# due_canshield.net
KiCad netlist of a schematic drawn in EAGLE
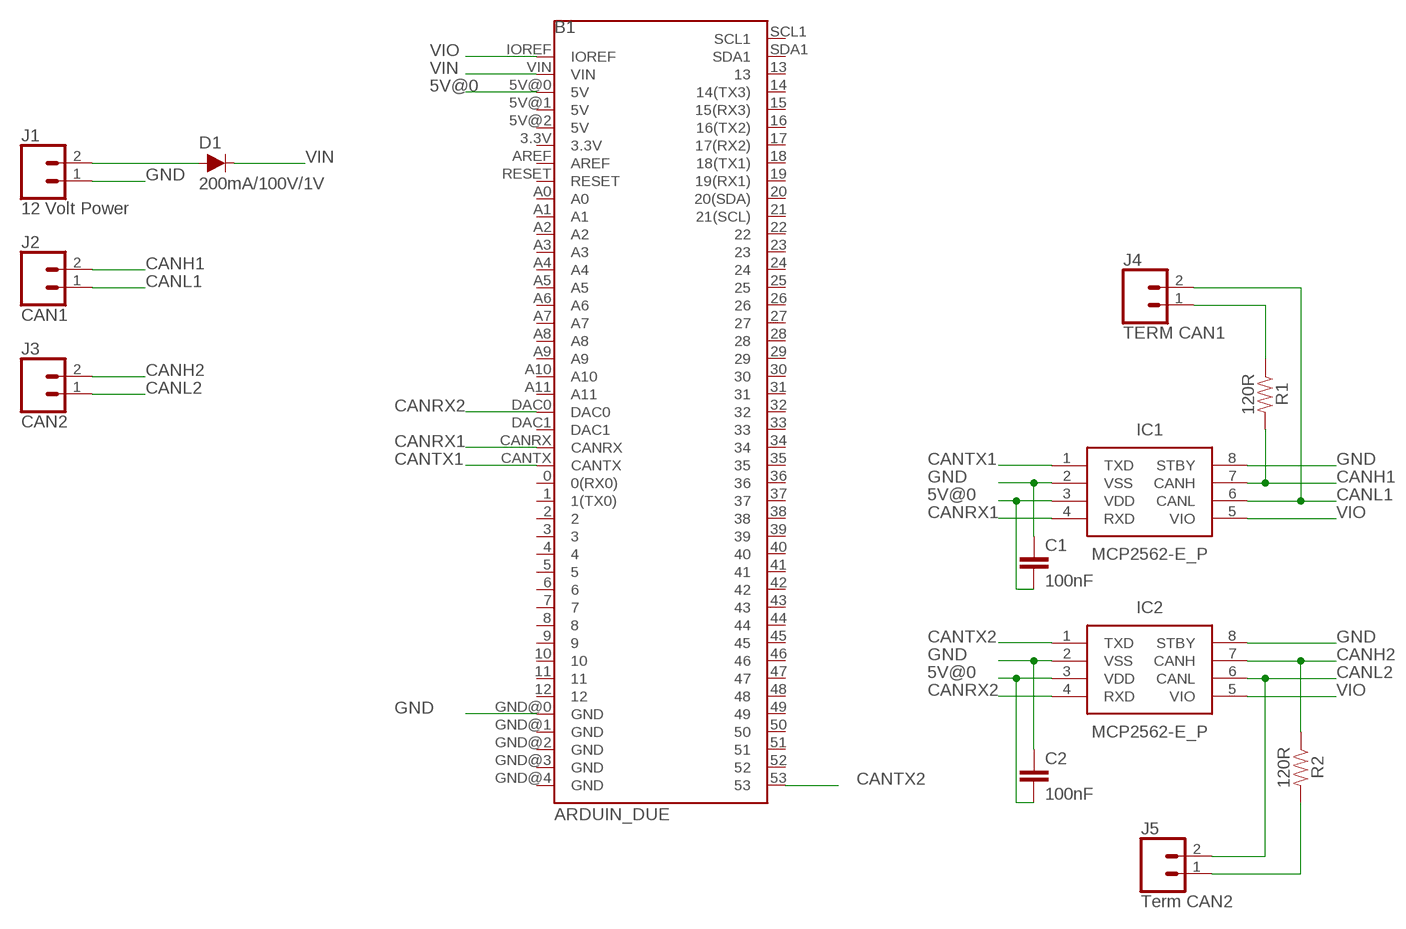
[diagram p0: schematic, sheet 1]

(export (version "E")
  (design (tool "Eeschema 10.0.6"))
  (components
    (comp (ref "B1")
      (value "ARDUIN_DUE")
      (footprint "eagle-import:ARDUINODUE")
      (libsource (lib "eagle-import") (part "ARDUIN_DUE"))
    )
    (comp (ref "C1")
      (value "100nF")
      (footprint "eagle-import:CAP-PTH-10MM")
      (libsource (lib "eagle-import") (part "10NF-PTH-10MM-10000V-1-%"))
    )
    (comp (ref "C2")
      (value "100nF")
      (footprint "eagle-import:CAP-PTH-10MM")
      (libsource (lib "eagle-import") (part "10NF-PTH-10MM-10000V-1-%"))
    )
    (comp (ref "D1")
      (value "200mA/100V/1V")
      (footprint "eagle-import:DIODE-1N4148")
      (libsource (lib "eagle-import") (part "DIODE-1N4148"))
    )
    (comp (ref "IC1")
      (value "MCP2562-E_P")
      (footprint "eagle-import:DIP781W56P254L950H533Q8N")
      (fields
        (field (name "MANUFACTURER_PART_NUMBER") "MCP2562-E/P")
        (field (name "RS_PART_NUMBER") "7990225")
      )
      (libsource (lib "eagle-import") (part "MCP2562-E_P"))
    )
    (comp (ref "IC2")
      (value "MCP2562-E_P")
      (footprint "eagle-import:DIP781W56P254L950H533Q8N")
      (fields
        (field (name "MANUFACTURER_PART_NUMBER") "MCP2562-E/P")
        (field (name "RS_PART_NUMBER") "7990225")
      )
      (libsource (lib "eagle-import") (part "MCP2562-E_P"))
    )
    (comp (ref "J1")
      (value "12 Volt Power")
      (footprint "eagle-import:SCREWTERMINAL-3.5MM-2")
      (libsource (lib "eagle-import") (part "SparkFun-Retired_CONN_023.5MM"))
    )
    (comp (ref "J2")
      (value "CAN1")
      (footprint "eagle-import:SCREWTERMINAL-3.5MM-2")
      (libsource (lib "eagle-import") (part "SparkFun-Retired_CONN_023.5MM"))
    )
    (comp (ref "J3")
      (value "CAN2")
      (footprint "eagle-import:SCREWTERMINAL-3.5MM-2")
      (libsource (lib "eagle-import") (part "SparkFun-Retired_CONN_023.5MM"))
    )
    (comp (ref "J4")
      (value "TERM CAN1")
      (footprint "eagle-import:1X02_LOCK_LONGPADS")
      (libsource (lib "eagle-import") (part "CONN_02LOCK_LONGPADS"))
    )
    (comp (ref "J5")
      (value "Term CAN2")
      (footprint "eagle-import:1X02_LOCK_LONGPADS")
      (libsource (lib "eagle-import") (part "CONN_02LOCK_LONGPADS"))
    )
    (comp (ref "R1")
      (value "120R")
      (footprint "eagle-import:AXIAL-0.3")
      (libsource (lib "eagle-import") (part "1KOHM-HORIZ-1/4W-5%"))
    )
    (comp (ref "R2")
      (value "120R")
      (footprint "eagle-import:AXIAL-0.3")
      (libsource (lib "eagle-import") (part "1KOHM-HORIZ-1/4W-5%"))
    )
  )
  (nets
    (net (code "1") (name "/5V@0") (class "Default")
      (node (ref "B1") (pin "5V@0") (pinfunction "5V_5V@0") (pintype "bidirectional"))
      (node (ref "C1") (pin "2") (pinfunction "2_2") (pintype "passive"))
      (node (ref "C2") (pin "2") (pinfunction "2_2") (pintype "passive"))
      (node (ref "IC1") (pin "3") (pinfunction "VDD_3") (pintype "passive"))
      (node (ref "IC2") (pin "3") (pinfunction "VDD_3") (pintype "passive"))
    )
    (net (code "2") (name "/CANH1") (class "Default")
      (node (ref "IC1") (pin "7") (pinfunction "CANH_7") (pintype "passive"))
      (node (ref "J2") (pin "2") (pinfunction "2_2") (pintype "passive"))
      (node (ref "R1") (pin "P$2") (pinfunction "2_P$2") (pintype "passive"))
    )
    (net (code "3") (name "/CANH2") (class "Default")
      (node (ref "IC2") (pin "7") (pinfunction "CANH_7") (pintype "passive"))
      (node (ref "J3") (pin "2") (pinfunction "2_2") (pintype "passive"))
      (node (ref "R2") (pin "P$1") (pinfunction "1_P$1") (pintype "passive"))
    )
    (net (code "4") (name "/CANL1") (class "Default")
      (node (ref "IC1") (pin "6") (pinfunction "CANL_6") (pintype "passive"))
      (node (ref "J2") (pin "1") (pinfunction "1_1") (pintype "passive"))
      (node (ref "J4") (pin "2") (pinfunction "2_2") (pintype "passive"))
    )
    (net (code "5") (name "/CANL2") (class "Default")
      (node (ref "IC2") (pin "6") (pinfunction "CANL_6") (pintype "passive"))
      (node (ref "J3") (pin "1") (pinfunction "1_1") (pintype "passive"))
      (node (ref "J5") (pin "2") (pinfunction "2_2") (pintype "passive"))
    )
    (net (code "6") (name "/CANRX1") (class "Default")
      (node (ref "B1") (pin "CANRX") (pinfunction "CANRX_CANRX") (pintype "bidirectional"))
      (node (ref "IC1") (pin "4") (pinfunction "RXD_4") (pintype "passive"))
    )
    (net (code "7") (name "/CANRX2") (class "Default")
      (node (ref "B1") (pin "DAC0") (pinfunction "DAC0_DAC0") (pintype "bidirectional"))
      (node (ref "IC2") (pin "4") (pinfunction "RXD_4") (pintype "passive"))
    )
    (net (code "8") (name "/CANTX1") (class "Default")
      (node (ref "B1") (pin "CANTX") (pinfunction "CANTX_CANTX") (pintype "bidirectional"))
      (node (ref "IC1") (pin "1") (pinfunction "TXD_1") (pintype "passive"))
    )
    (net (code "9") (name "/CANTX2") (class "Default")
      (node (ref "B1") (pin "53") (pinfunction "53_53") (pintype "bidirectional"))
      (node (ref "IC2") (pin "1") (pinfunction "TXD_1") (pintype "passive"))
    )
    (net (code "10") (name "/GND") (class "Default")
      (node (ref "B1") (pin "GND@0") (pinfunction "GND_GND@0") (pintype "bidirectional"))
      (node (ref "C1") (pin "1") (pinfunction "1_1") (pintype "passive"))
      (node (ref "C2") (pin "1") (pinfunction "1_1") (pintype "passive"))
      (node (ref "IC1") (pin "2") (pinfunction "VSS_2") (pintype "passive"))
      (node (ref "IC1") (pin "8") (pinfunction "STBY_8") (pintype "passive"))
      (node (ref "IC2") (pin "2") (pinfunction "VSS_2") (pintype "passive"))
      (node (ref "IC2") (pin "8") (pinfunction "STBY_8") (pintype "passive"))
      (node (ref "J1") (pin "1") (pinfunction "1_1") (pintype "passive"))
    )
    (net (code "11") (name "/VIN") (class "Default")
      (node (ref "B1") (pin "VIN") (pinfunction "VIN_VIN") (pintype "bidirectional"))
      (node (ref "D1") (pin "C") (pinfunction "C_C") (pintype "passive"))
    )
    (net (code "12") (name "/VIO") (class "Default")
      (node (ref "B1") (pin "IOREF") (pinfunction "IOREF_IOREF") (pintype "bidirectional"))
      (node (ref "IC1") (pin "5") (pinfunction "VIO_5") (pintype "passive"))
      (node (ref "IC2") (pin "5") (pinfunction "VIO_5") (pintype "passive"))
    )
    (net (code "13") (name "Net-(D1-PadA)") (class "Default")
      (node (ref "D1") (pin "A") (pinfunction "A_A") (pintype "passive"))
      (node (ref "J1") (pin "2") (pinfunction "2_2") (pintype "passive"))
    )
    (net (code "14") (name "Net-(R1-1)") (class "Default")
      (node (ref "J4") (pin "1") (pinfunction "1_1") (pintype "passive"))
      (node (ref "R1") (pin "P$1") (pinfunction "1_P$1") (pintype "passive"))
    )
    (net (code "15") (name "Net-(R2-2)") (class "Default")
      (node (ref "J5") (pin "1") (pinfunction "1_1") (pintype "passive"))
      (node (ref "R2") (pin "P$2") (pinfunction "2_P$2") (pintype "passive"))
    )
    (net (code "16") (name "unconnected-(B1-0(RX0)-Pad0)") (class "Default")
      (node (ref "B1") (pin "0") (pinfunction "0(RX0)_0") (pintype "bidirectional"))
    )
    (net (code "17") (name "unconnected-(B1-1(TX0)-Pad1)") (class "Default")
      (node (ref "B1") (pin "1") (pinfunction "1(TX0)_1") (pintype "bidirectional"))
    )
    (net (code "18") (name "unconnected-(B1-5V-Pad5V@1)") (class "Default")
      (node (ref "B1") (pin "5V@1") (pinfunction "5V_5V@1") (pintype "bidirectional"))
    )
    (net (code "19") (name "unconnected-(B1-5V-Pad5V@2)") (class "Default")
      (node (ref "B1") (pin "5V@2") (pinfunction "5V_5V@2") (pintype "bidirectional"))
    )
    (net (code "20") (name "unconnected-(B1-14(TX3)-Pad14)") (class "Default")
      (node (ref "B1") (pin "14") (pinfunction "14(TX3)_14") (pintype "bidirectional"))
    )
    (net (code "21") (name "unconnected-(B1-15(RX3)-Pad15)") (class "Default")
      (node (ref "B1") (pin "15") (pinfunction "15(RX3)_15") (pintype "bidirectional"))
    )
    (net (code "22") (name "unconnected-(B1-16(TX2)-Pad16)") (class "Default")
      (node (ref "B1") (pin "16") (pinfunction "16(TX2)_16") (pintype "bidirectional"))
    )
    (net (code "23") (name "unconnected-(B1-17(RX2)-Pad17)") (class "Default")
      (node (ref "B1") (pin "17") (pinfunction "17(RX2)_17") (pintype "bidirectional"))
    )
    (net (code "24") (name "unconnected-(B1-18(TX1)-Pad18)") (class "Default")
      (node (ref "B1") (pin "18") (pinfunction "18(TX1)_18") (pintype "bidirectional"))
    )
    (net (code "25") (name "unconnected-(B1-19(RX1)-Pad19)") (class "Default")
      (node (ref "B1") (pin "19") (pinfunction "19(RX1)_19") (pintype "bidirectional"))
    )
    (net (code "26") (name "unconnected-(B1-20(SDA)-Pad20)") (class "Default")
      (node (ref "B1") (pin "20") (pinfunction "20(SDA)_20") (pintype "bidirectional"))
    )
    (net (code "27") (name "unconnected-(B1-21(SCL)-Pad21)") (class "Default")
      (node (ref "B1") (pin "21") (pinfunction "21(SCL)_21") (pintype "bidirectional"))
    )
    (net (code "28") (name "unconnected-(B1-GND-PadGND@1)") (class "Default")
      (node (ref "B1") (pin "GND@1") (pinfunction "GND_GND@1") (pintype "bidirectional"))
    )
    (net (code "29") (name "unconnected-(B1-GND-PadGND@2)") (class "Default")
      (node (ref "B1") (pin "GND@2") (pinfunction "GND_GND@2") (pintype "bidirectional"))
    )
    (net (code "30") (name "unconnected-(B1-GND-PadGND@3)") (class "Default")
      (node (ref "B1") (pin "GND@3") (pinfunction "GND_GND@3") (pintype "bidirectional"))
    )
    (net (code "31") (name "unconnected-(B1-GND-PadGND@4)") (class "Default")
      (node (ref "B1") (pin "GND@4") (pinfunction "GND_GND@4") (pintype "bidirectional"))
    )
    (net (code "32") (name "unconnected-(B1-Pad2)") (class "Default")
      (node (ref "B1") (pin "2") (pinfunction "2_2") (pintype "bidirectional"))
    )
    (net (code "33") (name "unconnected-(B1-Pad3)") (class "Default")
      (node (ref "B1") (pin "3") (pinfunction "3_3") (pintype "bidirectional"))
    )
    (net (code "34") (name "unconnected-(B1-Pad3.3V)") (class "Default")
      (node (ref "B1") (pin "3.3V") (pinfunction "3.3V_3.3V") (pintype "bidirectional"))
    )
    (net (code "35") (name "unconnected-(B1-Pad4)") (class "Default")
      (node (ref "B1") (pin "4") (pinfunction "4_4") (pintype "bidirectional"))
    )
    (net (code "36") (name "unconnected-(B1-Pad5)") (class "Default")
      (node (ref "B1") (pin "5") (pinfunction "5_5") (pintype "bidirectional"))
    )
    (net (code "37") (name "unconnected-(B1-Pad6)") (class "Default")
      (node (ref "B1") (pin "6") (pinfunction "6_6") (pintype "bidirectional"))
    )
    (net (code "38") (name "unconnected-(B1-Pad7)") (class "Default")
      (node (ref "B1") (pin "7") (pinfunction "7_7") (pintype "bidirectional"))
    )
    (net (code "39") (name "unconnected-(B1-Pad8)") (class "Default")
      (node (ref "B1") (pin "8") (pinfunction "8_8") (pintype "bidirectional"))
    )
    (net (code "40") (name "unconnected-(B1-Pad9)") (class "Default")
      (node (ref "B1") (pin "9") (pinfunction "9_9") (pintype "bidirectional"))
    )
    (net (code "41") (name "unconnected-(B1-Pad10)") (class "Default")
      (node (ref "B1") (pin "10") (pinfunction "10_10") (pintype "bidirectional"))
    )
    (net (code "42") (name "unconnected-(B1-Pad11)") (class "Default")
      (node (ref "B1") (pin "11") (pinfunction "11_11") (pintype "bidirectional"))
    )
    (net (code "43") (name "unconnected-(B1-Pad12)") (class "Default")
      (node (ref "B1") (pin "12") (pinfunction "12_12") (pintype "bidirectional"))
    )
    (net (code "44") (name "unconnected-(B1-Pad13)") (class "Default")
      (node (ref "B1") (pin "13") (pinfunction "13_13") (pintype "bidirectional"))
    )
    (net (code "45") (name "unconnected-(B1-Pad22)") (class "Default")
      (node (ref "B1") (pin "22") (pinfunction "22_22") (pintype "bidirectional"))
    )
    (net (code "46") (name "unconnected-(B1-Pad23)") (class "Default")
      (node (ref "B1") (pin "23") (pinfunction "23_23") (pintype "bidirectional"))
    )
    (net (code "47") (name "unconnected-(B1-Pad24)") (class "Default")
      (node (ref "B1") (pin "24") (pinfunction "24_24") (pintype "bidirectional"))
    )
    (net (code "48") (name "unconnected-(B1-Pad25)") (class "Default")
      (node (ref "B1") (pin "25") (pinfunction "25_25") (pintype "bidirectional"))
    )
    (net (code "49") (name "unconnected-(B1-Pad26)") (class "Default")
      (node (ref "B1") (pin "26") (pinfunction "26_26") (pintype "bidirectional"))
    )
    (net (code "50") (name "unconnected-(B1-Pad27)") (class "Default")
      (node (ref "B1") (pin "27") (pinfunction "27_27") (pintype "bidirectional"))
    )
    (net (code "51") (name "unconnected-(B1-Pad28)") (class "Default")
      (node (ref "B1") (pin "28") (pinfunction "28_28") (pintype "bidirectional"))
    )
    (net (code "52") (name "unconnected-(B1-Pad29)") (class "Default")
      (node (ref "B1") (pin "29") (pinfunction "29_29") (pintype "bidirectional"))
    )
    (net (code "53") (name "unconnected-(B1-Pad30)") (class "Default")
      (node (ref "B1") (pin "30") (pinfunction "30_30") (pintype "bidirectional"))
    )
    (net (code "54") (name "unconnected-(B1-Pad31)") (class "Default")
      (node (ref "B1") (pin "31") (pinfunction "31_31") (pintype "bidirectional"))
    )
    (net (code "55") (name "unconnected-(B1-Pad32)") (class "Default")
      (node (ref "B1") (pin "32") (pinfunction "32_32") (pintype "bidirectional"))
    )
    (net (code "56") (name "unconnected-(B1-Pad33)") (class "Default")
      (node (ref "B1") (pin "33") (pinfunction "33_33") (pintype "bidirectional"))
    )
    (net (code "57") (name "unconnected-(B1-Pad34)") (class "Default")
      (node (ref "B1") (pin "34") (pinfunction "34_34") (pintype "bidirectional"))
    )
    (net (code "58") (name "unconnected-(B1-Pad35)") (class "Default")
      (node (ref "B1") (pin "35") (pinfunction "35_35") (pintype "bidirectional"))
    )
    (net (code "59") (name "unconnected-(B1-Pad36)") (class "Default")
      (node (ref "B1") (pin "36") (pinfunction "36_36") (pintype "bidirectional"))
    )
    (net (code "60") (name "unconnected-(B1-Pad37)") (class "Default")
      (node (ref "B1") (pin "37") (pinfunction "37_37") (pintype "bidirectional"))
    )
    (net (code "61") (name "unconnected-(B1-Pad38)") (class "Default")
      (node (ref "B1") (pin "38") (pinfunction "38_38") (pintype "bidirectional"))
    )
    (net (code "62") (name "unconnected-(B1-Pad39)") (class "Default")
      (node (ref "B1") (pin "39") (pinfunction "39_39") (pintype "bidirectional"))
    )
    (net (code "63") (name "unconnected-(B1-Pad40)") (class "Default")
      (node (ref "B1") (pin "40") (pinfunction "40_40") (pintype "bidirectional"))
    )
    (net (code "64") (name "unconnected-(B1-Pad41)") (class "Default")
      (node (ref "B1") (pin "41") (pinfunction "41_41") (pintype "bidirectional"))
    )
    (net (code "65") (name "unconnected-(B1-Pad42)") (class "Default")
      (node (ref "B1") (pin "42") (pinfunction "42_42") (pintype "bidirectional"))
    )
    (net (code "66") (name "unconnected-(B1-Pad43)") (class "Default")
      (node (ref "B1") (pin "43") (pinfunction "43_43") (pintype "bidirectional"))
    )
    (net (code "67") (name "unconnected-(B1-Pad44)") (class "Default")
      (node (ref "B1") (pin "44") (pinfunction "44_44") (pintype "bidirectional"))
    )
    (net (code "68") (name "unconnected-(B1-Pad45)") (class "Default")
      (node (ref "B1") (pin "45") (pinfunction "45_45") (pintype "bidirectional"))
    )
    (net (code "69") (name "unconnected-(B1-Pad46)") (class "Default")
      (node (ref "B1") (pin "46") (pinfunction "46_46") (pintype "bidirectional"))
    )
    (net (code "70") (name "unconnected-(B1-Pad47)") (class "Default")
      (node (ref "B1") (pin "47") (pinfunction "47_47") (pintype "bidirectional"))
    )
    (net (code "71") (name "unconnected-(B1-Pad48)") (class "Default")
      (node (ref "B1") (pin "48") (pinfunction "48_48") (pintype "bidirectional"))
    )
    (net (code "72") (name "unconnected-(B1-Pad49)") (class "Default")
      (node (ref "B1") (pin "49") (pinfunction "49_49") (pintype "bidirectional"))
    )
    (net (code "73") (name "unconnected-(B1-Pad50)") (class "Default")
      (node (ref "B1") (pin "50") (pinfunction "50_50") (pintype "bidirectional"))
    )
    (net (code "74") (name "unconnected-(B1-Pad51)") (class "Default")
      (node (ref "B1") (pin "51") (pinfunction "51_51") (pintype "bidirectional"))
    )
    (net (code "75") (name "unconnected-(B1-Pad52)") (class "Default")
      (node (ref "B1") (pin "52") (pinfunction "52_52") (pintype "bidirectional"))
    )
    (net (code "76") (name "unconnected-(B1-PadA0)") (class "Default")
      (node (ref "B1") (pin "A0") (pinfunction "A0_A0") (pintype "bidirectional"))
    )
    (net (code "77") (name "unconnected-(B1-PadA1)") (class "Default")
      (node (ref "B1") (pin "A1") (pinfunction "A1_A1") (pintype "bidirectional"))
    )
    (net (code "78") (name "unconnected-(B1-PadA2)") (class "Default")
      (node (ref "B1") (pin "A2") (pinfunction "A2_A2") (pintype "bidirectional"))
    )
    (net (code "79") (name "unconnected-(B1-PadA3)") (class "Default")
      (node (ref "B1") (pin "A3") (pinfunction "A3_A3") (pintype "bidirectional"))
    )
    (net (code "80") (name "unconnected-(B1-PadA4)") (class "Default")
      (node (ref "B1") (pin "A4") (pinfunction "A4_A4") (pintype "bidirectional"))
    )
    (net (code "81") (name "unconnected-(B1-PadA5)") (class "Default")
      (node (ref "B1") (pin "A5") (pinfunction "A5_A5") (pintype "bidirectional"))
    )
    (net (code "82") (name "unconnected-(B1-PadA6)") (class "Default")
      (node (ref "B1") (pin "A6") (pinfunction "A6_A6") (pintype "bidirectional"))
    )
    (net (code "83") (name "unconnected-(B1-PadA7)") (class "Default")
      (node (ref "B1") (pin "A7") (pinfunction "A7_A7") (pintype "bidirectional"))
    )
    (net (code "84") (name "unconnected-(B1-PadA8)") (class "Default")
      (node (ref "B1") (pin "A8") (pinfunction "A8_A8") (pintype "bidirectional"))
    )
    (net (code "85") (name "unconnected-(B1-PadA9)") (class "Default")
      (node (ref "B1") (pin "A9") (pinfunction "A9_A9") (pintype "bidirectional"))
    )
    (net (code "86") (name "unconnected-(B1-PadA10)") (class "Default")
      (node (ref "B1") (pin "A10") (pinfunction "A10_A10") (pintype "bidirectional"))
    )
    (net (code "87") (name "unconnected-(B1-PadA11)") (class "Default")
      (node (ref "B1") (pin "A11") (pinfunction "A11_A11") (pintype "bidirectional"))
    )
    (net (code "88") (name "unconnected-(B1-PadAREF)") (class "Default")
      (node (ref "B1") (pin "AREF") (pinfunction "AREF_AREF") (pintype "bidirectional"))
    )
    (net (code "89") (name "unconnected-(B1-PadDAC1)") (class "Default")
      (node (ref "B1") (pin "DAC1") (pinfunction "DAC1_DAC1") (pintype "bidirectional"))
    )
    (net (code "90") (name "unconnected-(B1-PadRESET)") (class "Default")
      (node (ref "B1") (pin "RESET") (pinfunction "RESET_RESET") (pintype "bidirectional"))
    )
    (net (code "91") (name "unconnected-(B1-PadSCL1)") (class "Default")
      (node (ref "B1") (pin "SCL1") (pinfunction "SCL1_SCL1") (pintype "bidirectional"))
    )
    (net (code "92") (name "unconnected-(B1-PadSDA1)") (class "Default")
      (node (ref "B1") (pin "SDA1") (pinfunction "SDA1_SDA1") (pintype "bidirectional"))
    )
  )
)
